# board.net
KiCad netlist of a schematic drawn in EAGLE
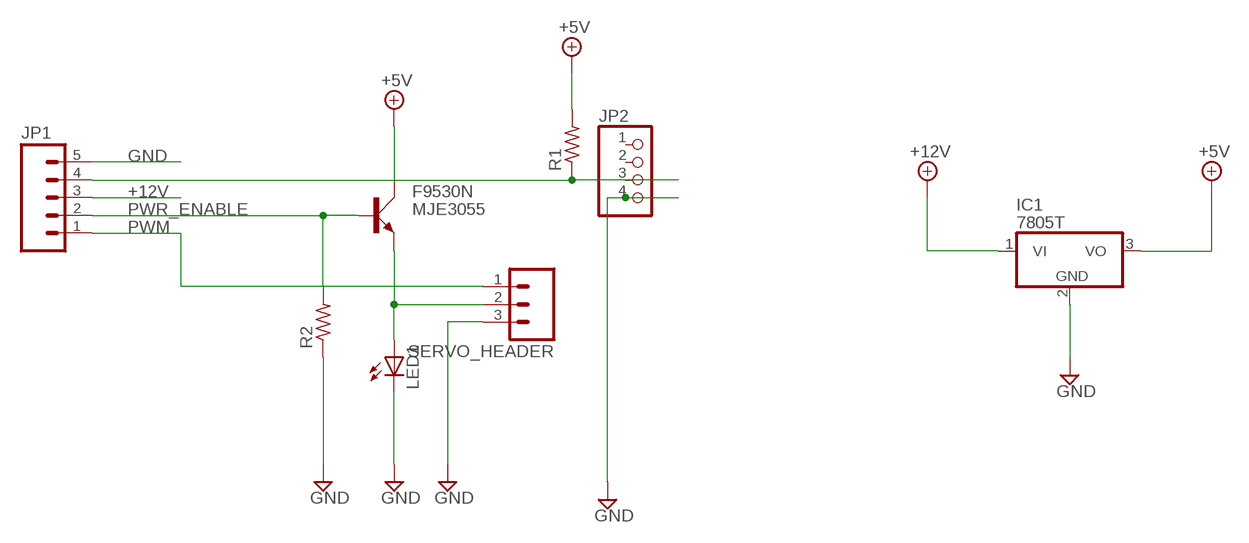
[diagram p0: schematic, sheet 1]

(export (version "E")
  (design (tool "Eeschema 10.0.6"))
  (components
    (comp (ref "F9530N")
      (value "MJE3055")
      (footprint "eagle-import:TO220AV")
      (libsource (lib "eagle-import") (part "MJE3055"))
    )
    (comp (ref "IC1")
      (value "7805T")
      (footprint "eagle-import:TO220H")
      (libsource (lib "eagle-import") (part "78T05"))
    )
    (comp (ref "JP1")
      (value "M05PTH")
      (footprint "eagle-import:1X05")
      (libsource (lib "eagle-import") (part "M05PTH"))
    )
    (comp (ref "JP2")
      (value "PINHD-1X4")
      (footprint "eagle-import:1X04")
      (libsource (lib "eagle-import") (part "PINHD-1X4"))
    )
    (comp (ref "LED1")
      (value "LED")
      (footprint "eagle-import:SMARTLED-TTW")
      (libsource (lib "eagle-import") (part "LED"))
    )
    (comp (ref "R1")
      (value "R-US_0204/7")
      (footprint "eagle-import:0204_7")
      (libsource (lib "eagle-import") (part "R-US_0204/7"))
    )
    (comp (ref "R2")
      (value "R-US_0204/7")
      (footprint "eagle-import:0204_7")
      (libsource (lib "eagle-import") (part "R-US_0204/7"))
    )
    (comp (ref "SERVO_HEADER")
      (value "M03PTH")
      (footprint "eagle-import:1X03")
      (libsource (lib "eagle-import") (part "M03PTH"))
    )
  )
  (nets
    (net (code "1") (name "+5V") (class "Default")
      (node (ref "F9530N") (pin "C") (pinfunction "C_C") (pintype "passive"))
      (node (ref "IC1") (pin "3") (pinfunction "VO_3") (pintype "passive"))
      (node (ref "R1") (pin "2") (pinfunction "2_2") (pintype "passive"))
    )
    (net (code "2") (name "+12V") (class "Default")
      (node (ref "IC1") (pin "1") (pinfunction "VI_1") (pintype "input"))
      (node (ref "JP1") (pin "3") (pinfunction "3_3") (pintype "passive"))
    )
    (net (code "3") (name "/PWM") (class "Default")
      (node (ref "JP1") (pin "1") (pinfunction "1_1") (pintype "passive"))
      (node (ref "SERVO_HEADER") (pin "1") (pinfunction "1_1") (pintype "passive"))
    )
    (net (code "4") (name "/PWR_ENABLE") (class "Default")
      (node (ref "F9530N") (pin "B") (pinfunction "B_B") (pintype "passive"))
      (node (ref "JP1") (pin "2") (pinfunction "2_2") (pintype "passive"))
      (node (ref "R2") (pin "2") (pinfunction "2_2") (pintype "passive"))
    )
    (net (code "5") (name "GND") (class "Default")
      (node (ref "IC1") (pin "2") (pinfunction "GND_2") (pintype "passive"))
      (node (ref "JP1") (pin "5") (pinfunction "5_5") (pintype "passive"))
      (node (ref "JP2") (pin "4") (pinfunction "4_4") (pintype "passive"))
      (node (ref "LED1") (pin "C@1") (pinfunction "C_C@1") (pintype "passive"))
      (node (ref "R2") (pin "1") (pinfunction "1_1") (pintype "passive"))
      (node (ref "SERVO_HEADER") (pin "3") (pinfunction "3_3") (pintype "passive"))
    )
    (net (code "6") (name "Net-(JP1-Pad4)") (class "Default")
      (node (ref "JP1") (pin "4") (pinfunction "4_4") (pintype "passive"))
      (node (ref "R1") (pin "1") (pinfunction "1_1") (pintype "passive"))
    )
    (net (code "7") (name "Net-(LED1-A)") (class "Default")
      (node (ref "F9530N") (pin "E") (pinfunction "E_E") (pintype "passive"))
      (node (ref "LED1") (pin "A@1") (pinfunction "A_A@1") (pintype "passive"))
      (node (ref "SERVO_HEADER") (pin "2") (pinfunction "2_2") (pintype "passive"))
    )
    (net (code "8") (name "unconnected-(JP2-Pad1)") (class "Default")
      (node (ref "JP2") (pin "1") (pinfunction "1_1") (pintype "passive"))
    )
    (net (code "9") (name "unconnected-(JP2-Pad2)") (class "Default")
      (node (ref "JP2") (pin "2") (pinfunction "2_2") (pintype "passive"))
    )
    (net (code "10") (name "unconnected-(JP2-Pad3)") (class "Default")
      (node (ref "JP2") (pin "3") (pinfunction "3_3") (pintype "passive"))
    )
  )
)
